# Sensor_Decoderv0_5.net
KiCad netlist of a schematic drawn in EAGLE
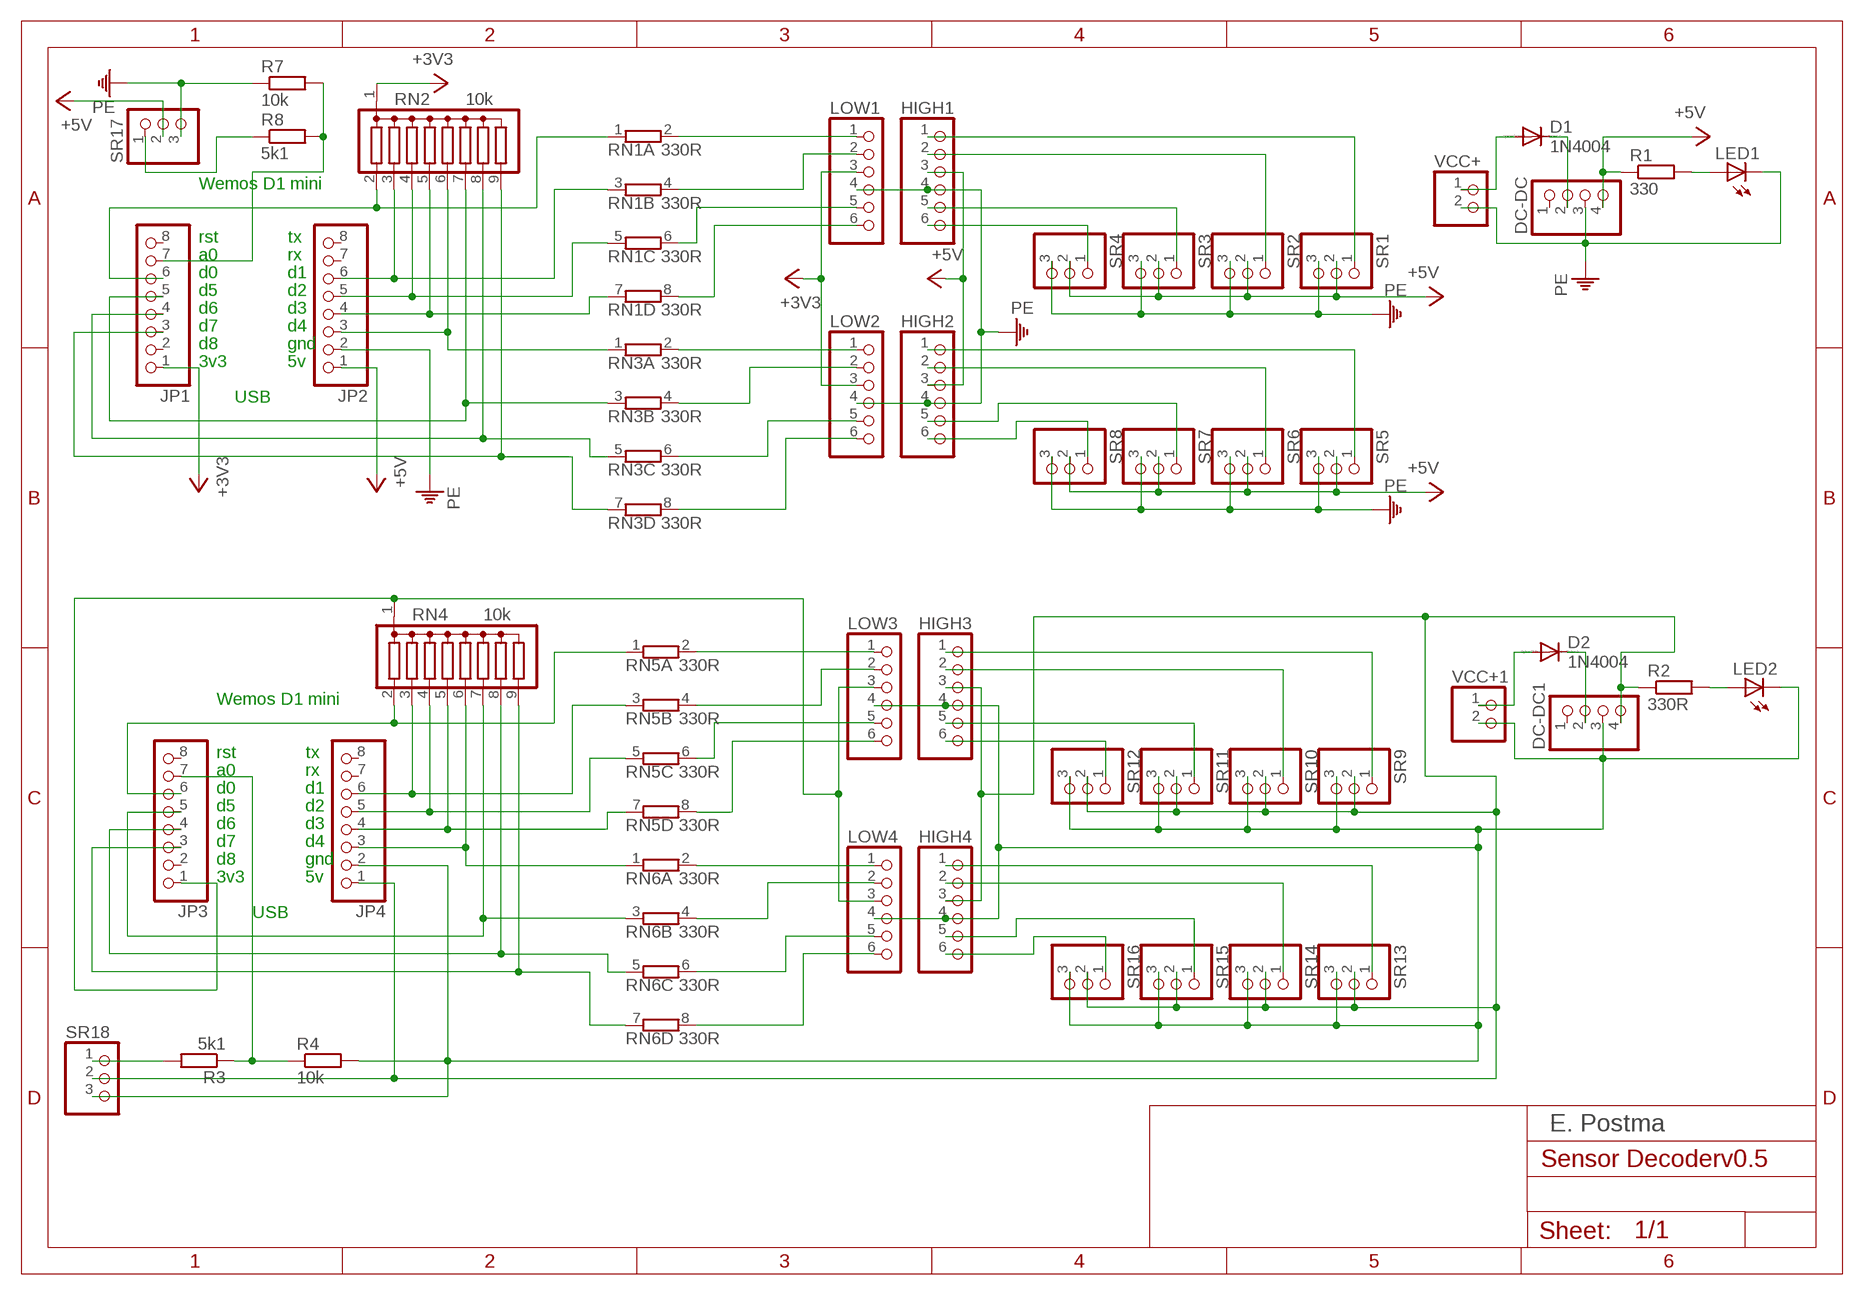
[diagram p0: schematic, sheet 1]

(export (version "E")
  (design (tool "Eeschema 10.0.6"))
  (components
    (comp (ref "D1")
      (value "1N4004")
      (footprint "eagle-import:DO41-10")
      (libsource (lib "eagle-import") (part "1N4004"))
    )
    (comp (ref "D2")
      (value "1N4004")
      (footprint "eagle-import:DO41-10")
      (libsource (lib "eagle-import") (part "1N4004"))
    )
    (comp (ref "DC-DC")
      (value "PINHD-1X4")
      (footprint "eagle-import:1X04")
      (libsource (lib "eagle-import") (part "PINHD-1X4"))
    )
    (comp (ref "DC-DC1")
      (value "PINHD-1X4")
      (footprint "eagle-import:1X04")
      (libsource (lib "eagle-import") (part "PINHD-1X4"))
    )
    (comp (ref "HIGH1")
      (value "PINHD-1X6")
      (footprint "eagle-import:1X06")
      (libsource (lib "eagle-import") (part "PINHD-1X6"))
    )
    (comp (ref "HIGH2")
      (value "PINHD-1X6")
      (footprint "eagle-import:1X06")
      (libsource (lib "eagle-import") (part "PINHD-1X6"))
    )
    (comp (ref "HIGH3")
      (value "PINHD-1X6")
      (footprint "eagle-import:1X06")
      (libsource (lib "eagle-import") (part "PINHD-1X6"))
    )
    (comp (ref "HIGH4")
      (value "PINHD-1X6")
      (footprint "eagle-import:1X06")
      (libsource (lib "eagle-import") (part "PINHD-1X6"))
    )
    (comp (ref "JP1")
      (value "PINHD-1X8")
      (footprint "eagle-import:1X08")
      (libsource (lib "eagle-import") (part "PINHD-1X8"))
    )
    (comp (ref "JP2")
      (value "PINHD-1X8")
      (footprint "eagle-import:1X08")
      (libsource (lib "eagle-import") (part "PINHD-1X8"))
    )
    (comp (ref "JP3")
      (value "PINHD-1X8")
      (footprint "eagle-import:1X08")
      (libsource (lib "eagle-import") (part "PINHD-1X8"))
    )
    (comp (ref "JP4")
      (value "PINHD-1X8")
      (footprint "eagle-import:1X08")
      (libsource (lib "eagle-import") (part "PINHD-1X8"))
    )
    (comp (ref "LED1")
      (value "LED3MM")
      (footprint "eagle-import:LED3MM")
      (libsource (lib "eagle-import") (part "LED3MM"))
    )
    (comp (ref "LED2")
      (value "LED3MM")
      (footprint "eagle-import:LED3MM")
      (libsource (lib "eagle-import") (part "LED3MM"))
    )
    (comp (ref "LOW1")
      (value "PINHD-1X6")
      (footprint "eagle-import:1X06")
      (libsource (lib "eagle-import") (part "PINHD-1X6"))
    )
    (comp (ref "LOW2")
      (value "PINHD-1X6")
      (footprint "eagle-import:1X06")
      (libsource (lib "eagle-import") (part "PINHD-1X6"))
    )
    (comp (ref "LOW3")
      (value "PINHD-1X6")
      (footprint "eagle-import:1X06")
      (libsource (lib "eagle-import") (part "PINHD-1X6"))
    )
    (comp (ref "LOW4")
      (value "PINHD-1X6")
      (footprint "eagle-import:1X06")
      (libsource (lib "eagle-import") (part "PINHD-1X6"))
    )
    (comp (ref "R1")
      (value "330")
      (footprint "eagle-import:0207_7")
      (libsource (lib "eagle-import") (part "R-EU_0207/7"))
    )
    (comp (ref "R2")
      (value "330R")
      (footprint "eagle-import:0207_7")
      (libsource (lib "eagle-import") (part "R-EU_0207/7"))
    )
    (comp (ref "R3")
      (value "5k1")
      (footprint "eagle-import:0207_7")
      (libsource (lib "eagle-import") (part "R-EU_0207/7"))
    )
    (comp (ref "R4")
      (value "10k")
      (footprint "eagle-import:0207_7")
      (libsource (lib "eagle-import") (part "R-EU_0207/7"))
    )
    (comp (ref "R7")
      (value "10k")
      (footprint "eagle-import:0207_7")
      (libsource (lib "eagle-import") (part "R-EU_0207/7"))
    )
    (comp (ref "R8")
      (value "5k1")
      (footprint "eagle-import:0207_7")
      (libsource (lib "eagle-import") (part "R-EU_0207/7"))
    )
    (comp (ref "RN1")
      (value "330R")
      (footprint "eagle-import:SIL8")
      (libsource (lib "eagle-import") (part "E4R"))
    )
    (comp (ref "RN2")
      (value "10k")
      (footprint "eagle-import:SIL9")
      (libsource (lib "eagle-import") (part "G08R"))
    )
    (comp (ref "RN3")
      (value "330R")
      (footprint "eagle-import:SIL8")
      (libsource (lib "eagle-import") (part "E4R"))
    )
    (comp (ref "RN4")
      (value "10k")
      (footprint "eagle-import:SIL9")
      (libsource (lib "eagle-import") (part "G08R"))
    )
    (comp (ref "RN5")
      (value "330R")
      (footprint "eagle-import:SIL8")
      (libsource (lib "eagle-import") (part "E4R"))
    )
    (comp (ref "RN6")
      (value "330R")
      (footprint "eagle-import:SIL8")
      (libsource (lib "eagle-import") (part "E4R"))
    )
    (comp (ref "SR1")
      (value "PINHD-1X3")
      (footprint "eagle-import:1X03")
      (libsource (lib "eagle-import") (part "PINHD-1X3"))
    )
    (comp (ref "SR2")
      (value "PINHD-1X3")
      (footprint "eagle-import:1X03")
      (libsource (lib "eagle-import") (part "PINHD-1X3"))
    )
    (comp (ref "SR3")
      (value "PINHD-1X3")
      (footprint "eagle-import:1X03")
      (libsource (lib "eagle-import") (part "PINHD-1X3"))
    )
    (comp (ref "SR4")
      (value "PINHD-1X3")
      (footprint "eagle-import:1X03")
      (libsource (lib "eagle-import") (part "PINHD-1X3"))
    )
    (comp (ref "SR5")
      (value "PINHD-1X3")
      (footprint "eagle-import:1X03")
      (libsource (lib "eagle-import") (part "PINHD-1X3"))
    )
    (comp (ref "SR6")
      (value "PINHD-1X3")
      (footprint "eagle-import:1X03")
      (libsource (lib "eagle-import") (part "PINHD-1X3"))
    )
    (comp (ref "SR7")
      (value "PINHD-1X3")
      (footprint "eagle-import:1X03")
      (libsource (lib "eagle-import") (part "PINHD-1X3"))
    )
    (comp (ref "SR8")
      (value "PINHD-1X3")
      (footprint "eagle-import:1X03")
      (libsource (lib "eagle-import") (part "PINHD-1X3"))
    )
    (comp (ref "SR9")
      (value "PINHD-1X3")
      (footprint "eagle-import:1X03")
      (libsource (lib "eagle-import") (part "PINHD-1X3"))
    )
    (comp (ref "SR10")
      (value "PINHD-1X3")
      (footprint "eagle-import:1X03")
      (libsource (lib "eagle-import") (part "PINHD-1X3"))
    )
    (comp (ref "SR11")
      (value "PINHD-1X3")
      (footprint "eagle-import:1X03")
      (libsource (lib "eagle-import") (part "PINHD-1X3"))
    )
    (comp (ref "SR12")
      (value "PINHD-1X3")
      (footprint "eagle-import:1X03")
      (libsource (lib "eagle-import") (part "PINHD-1X3"))
    )
    (comp (ref "SR13")
      (value "PINHD-1X3")
      (footprint "eagle-import:1X03")
      (libsource (lib "eagle-import") (part "PINHD-1X3"))
    )
    (comp (ref "SR14")
      (value "PINHD-1X3")
      (footprint "eagle-import:1X03")
      (libsource (lib "eagle-import") (part "PINHD-1X3"))
    )
    (comp (ref "SR15")
      (value "PINHD-1X3")
      (footprint "eagle-import:1X03")
      (libsource (lib "eagle-import") (part "PINHD-1X3"))
    )
    (comp (ref "SR16")
      (value "PINHD-1X3")
      (footprint "eagle-import:1X03")
      (libsource (lib "eagle-import") (part "PINHD-1X3"))
    )
    (comp (ref "SR17")
      (value "PINHD-1X3")
      (footprint "eagle-import:1X03")
      (libsource (lib "eagle-import") (part "PINHD-1X3"))
    )
    (comp (ref "SR18")
      (value "PINHD-1X3")
      (footprint "eagle-import:1X03")
      (libsource (lib "eagle-import") (part "PINHD-1X3"))
    )
    (comp (ref "VCC+")
      (value "PINHD-1X2")
      (footprint "eagle-import:1X02")
      (libsource (lib "eagle-import") (part "PINHD-1X2"))
    )
    (comp (ref "VCC+1")
      (value "PINHD-1X2")
      (footprint "eagle-import:1X02")
      (libsource (lib "eagle-import") (part "PINHD-1X2"))
    )
  )
  (nets
    (net (code "1") (name "+3V3") (class "Default")
      (node (ref "JP1") (pin "1") (pinfunction "1_1") (pintype "passive"))
      (node (ref "LOW1") (pin "3") (pinfunction "3_3") (pintype "passive"))
      (node (ref "LOW2") (pin "3") (pinfunction "3_3") (pintype "passive"))
      (node (ref "RN2") (pin "1") (pinfunction "1_1") (pintype "passive"))
    )
    (net (code "2") (name "+5V") (class "Default")
      (node (ref "DC-DC") (pin "4") (pinfunction "4_4") (pintype "passive"))
      (node (ref "HIGH1") (pin "3") (pinfunction "3_3") (pintype "passive"))
      (node (ref "HIGH2") (pin "3") (pinfunction "3_3") (pintype "passive"))
      (node (ref "JP2") (pin "1") (pinfunction "1_1") (pintype "passive"))
      (node (ref "R1") (pin "1") (pinfunction "1_1") (pintype "passive"))
      (node (ref "SR1") (pin "2") (pinfunction "2_2") (pintype "passive"))
      (node (ref "SR17") (pin "2") (pinfunction "2_2") (pintype "passive"))
      (node (ref "SR2") (pin "2") (pinfunction "2_2") (pintype "passive"))
      (node (ref "SR3") (pin "2") (pinfunction "2_2") (pintype "passive"))
      (node (ref "SR4") (pin "2") (pinfunction "2_2") (pintype "passive"))
      (node (ref "SR5") (pin "2") (pinfunction "2_2") (pintype "passive"))
      (node (ref "SR6") (pin "2") (pinfunction "2_2") (pintype "passive"))
      (node (ref "SR7") (pin "2") (pinfunction "2_2") (pintype "passive"))
      (node (ref "SR8") (pin "2") (pinfunction "2_2") (pintype "passive"))
    )
    (net (code "3") (name "Net-(D1-PadA)") (class "Default")
      (node (ref "D1") (pin "A") (pinfunction "A_A") (pintype "passive"))
      (node (ref "VCC+") (pin "1") (pinfunction "1_1") (pintype "passive"))
    )
    (net (code "4") (name "Net-(D1-PadC)") (class "Default")
      (node (ref "D1") (pin "C") (pinfunction "C_C") (pintype "passive"))
      (node (ref "DC-DC") (pin "2") (pinfunction "2_2") (pintype "passive"))
    )
    (net (code "5") (name "Net-(D2-PadA)") (class "Default")
      (node (ref "D2") (pin "A") (pinfunction "A_A") (pintype "passive"))
      (node (ref "VCC+1") (pin "1") (pinfunction "1_1") (pintype "passive"))
    )
    (net (code "6") (name "Net-(D2-PadC)") (class "Default")
      (node (ref "D2") (pin "C") (pinfunction "C_C") (pintype "passive"))
      (node (ref "DC-DC1") (pin "2") (pinfunction "2_2") (pintype "passive"))
    )
    (net (code "7") (name "Net-(DC-DC1-Pad4)") (class "Default")
      (node (ref "DC-DC1") (pin "4") (pinfunction "4_4") (pintype "passive"))
      (node (ref "HIGH3") (pin "3") (pinfunction "3_3") (pintype "passive"))
      (node (ref "HIGH4") (pin "3") (pinfunction "3_3") (pintype "passive"))
      (node (ref "JP4") (pin "1") (pinfunction "1_1") (pintype "passive"))
      (node (ref "R2") (pin "1") (pinfunction "1_1") (pintype "passive"))
      (node (ref "SR10") (pin "2") (pinfunction "2_2") (pintype "passive"))
      (node (ref "SR11") (pin "2") (pinfunction "2_2") (pintype "passive"))
      (node (ref "SR12") (pin "2") (pinfunction "2_2") (pintype "passive"))
      (node (ref "SR13") (pin "2") (pinfunction "2_2") (pintype "passive"))
      (node (ref "SR14") (pin "2") (pinfunction "2_2") (pintype "passive"))
      (node (ref "SR15") (pin "2") (pinfunction "2_2") (pintype "passive"))
      (node (ref "SR16") (pin "2") (pinfunction "2_2") (pintype "passive"))
      (node (ref "SR18") (pin "2") (pinfunction "2_2") (pintype "passive"))
      (node (ref "SR9") (pin "2") (pinfunction "2_2") (pintype "passive"))
    )
    (net (code "8") (name "Net-(HIGH1-Pad1)") (class "Default")
      (node (ref "HIGH1") (pin "1") (pinfunction "1_1") (pintype "passive"))
      (node (ref "SR1") (pin "1") (pinfunction "1_1") (pintype "passive"))
    )
    (net (code "9") (name "Net-(HIGH1-Pad2)") (class "Default")
      (node (ref "HIGH1") (pin "2") (pinfunction "2_2") (pintype "passive"))
      (node (ref "SR2") (pin "1") (pinfunction "1_1") (pintype "passive"))
    )
    (net (code "10") (name "Net-(HIGH1-Pad5)") (class "Default")
      (node (ref "HIGH1") (pin "5") (pinfunction "5_5") (pintype "passive"))
      (node (ref "SR3") (pin "1") (pinfunction "1_1") (pintype "passive"))
    )
    (net (code "11") (name "Net-(HIGH1-Pad6)") (class "Default")
      (node (ref "HIGH1") (pin "6") (pinfunction "6_6") (pintype "passive"))
      (node (ref "SR4") (pin "1") (pinfunction "1_1") (pintype "passive"))
    )
    (net (code "12") (name "Net-(HIGH2-Pad1)") (class "Default")
      (node (ref "HIGH2") (pin "1") (pinfunction "1_1") (pintype "passive"))
      (node (ref "SR5") (pin "1") (pinfunction "1_1") (pintype "passive"))
    )
    (net (code "13") (name "Net-(HIGH2-Pad2)") (class "Default")
      (node (ref "HIGH2") (pin "2") (pinfunction "2_2") (pintype "passive"))
      (node (ref "SR6") (pin "1") (pinfunction "1_1") (pintype "passive"))
    )
    (net (code "14") (name "Net-(HIGH2-Pad5)") (class "Default")
      (node (ref "HIGH2") (pin "5") (pinfunction "5_5") (pintype "passive"))
      (node (ref "SR7") (pin "1") (pinfunction "1_1") (pintype "passive"))
    )
    (net (code "15") (name "Net-(HIGH2-Pad6)") (class "Default")
      (node (ref "HIGH2") (pin "6") (pinfunction "6_6") (pintype "passive"))
      (node (ref "SR8") (pin "1") (pinfunction "1_1") (pintype "passive"))
    )
    (net (code "16") (name "Net-(HIGH3-Pad1)") (class "Default")
      (node (ref "HIGH3") (pin "1") (pinfunction "1_1") (pintype "passive"))
      (node (ref "SR9") (pin "1") (pinfunction "1_1") (pintype "passive"))
    )
    (net (code "17") (name "Net-(HIGH3-Pad2)") (class "Default")
      (node (ref "HIGH3") (pin "2") (pinfunction "2_2") (pintype "passive"))
      (node (ref "SR10") (pin "1") (pinfunction "1_1") (pintype "passive"))
    )
    (net (code "18") (name "Net-(HIGH3-Pad5)") (class "Default")
      (node (ref "HIGH3") (pin "5") (pinfunction "5_5") (pintype "passive"))
      (node (ref "SR11") (pin "1") (pinfunction "1_1") (pintype "passive"))
    )
    (net (code "19") (name "Net-(HIGH3-Pad6)") (class "Default")
      (node (ref "HIGH3") (pin "6") (pinfunction "6_6") (pintype "passive"))
      (node (ref "SR12") (pin "1") (pinfunction "1_1") (pintype "passive"))
    )
    (net (code "20") (name "Net-(HIGH4-Pad1)") (class "Default")
      (node (ref "HIGH4") (pin "1") (pinfunction "1_1") (pintype "passive"))
      (node (ref "SR13") (pin "1") (pinfunction "1_1") (pintype "passive"))
    )
    (net (code "21") (name "Net-(HIGH4-Pad2)") (class "Default")
      (node (ref "HIGH4") (pin "2") (pinfunction "2_2") (pintype "passive"))
      (node (ref "SR14") (pin "1") (pinfunction "1_1") (pintype "passive"))
    )
    (net (code "22") (name "Net-(HIGH4-Pad5)") (class "Default")
      (node (ref "HIGH4") (pin "5") (pinfunction "5_5") (pintype "passive"))
      (node (ref "SR15") (pin "1") (pinfunction "1_1") (pintype "passive"))
    )
    (net (code "23") (name "Net-(HIGH4-Pad6)") (class "Default")
      (node (ref "HIGH4") (pin "6") (pinfunction "6_6") (pintype "passive"))
      (node (ref "SR16") (pin "1") (pinfunction "1_1") (pintype "passive"))
    )
    (net (code "24") (name "Net-(JP1-Pad6)") (class "Default")
      (node (ref "JP1") (pin "6") (pinfunction "6_6") (pintype "passive"))
      (node (ref "RN1") (pin "1") (pinfunction "1_1") (pintype "passive"))
      (node (ref "RN2") (pin "2") (pinfunction "2_2") (pintype "passive"))
    )
    (net (code "25") (name "Net-(JP1-Pad7)") (class "Default")
      (node (ref "JP1") (pin "7") (pinfunction "7_7") (pintype "passive"))
      (node (ref "R7") (pin "2") (pinfunction "2_2") (pintype "passive"))
      (node (ref "R8") (pin "2") (pinfunction "2_2") (pintype "passive"))
    )
    (net (code "26") (name "Net-(JP2-Pad3)") (class "Default")
      (node (ref "JP2") (pin "3") (pinfunction "3_3") (pintype "passive"))
      (node (ref "RN2") (pin "6") (pinfunction "6_6") (pintype "passive"))
      (node (ref "RN3") (pin "1") (pinfunction "1_1") (pintype "passive"))
    )
    (net (code "27") (name "Net-(JP3-Pad1)") (class "Default")
      (node (ref "JP3") (pin "1") (pinfunction "1_1") (pintype "passive"))
      (node (ref "LOW3") (pin "3") (pinfunction "3_3") (pintype "passive"))
      (node (ref "LOW4") (pin "3") (pinfunction "3_3") (pintype "passive"))
      (node (ref "RN4") (pin "1") (pinfunction "1_1") (pintype "passive"))
    )
    (net (code "28") (name "Net-(JP3-Pad6)") (class "Default")
      (node (ref "JP3") (pin "6") (pinfunction "6_6") (pintype "passive"))
      (node (ref "RN4") (pin "2") (pinfunction "2_2") (pintype "passive"))
      (node (ref "RN5") (pin "1") (pinfunction "1_1") (pintype "passive"))
    )
    (net (code "29") (name "Net-(JP3-Pad7)") (class "Default")
      (node (ref "JP3") (pin "7") (pinfunction "7_7") (pintype "passive"))
      (node (ref "R3") (pin "1") (pinfunction "1_1") (pintype "passive"))
      (node (ref "R4") (pin "1") (pinfunction "1_1") (pintype "passive"))
    )
    (net (code "30") (name "Net-(JP4-Pad3)") (class "Default")
      (node (ref "JP4") (pin "3") (pinfunction "3_3") (pintype "passive"))
      (node (ref "RN4") (pin "6") (pinfunction "6_6") (pintype "passive"))
      (node (ref "RN6") (pin "1") (pinfunction "1_1") (pintype "passive"))
    )
    (net (code "31") (name "Net-(LED1-PadA)") (class "Default")
      (node (ref "LED1") (pin "A") (pinfunction "A_A") (pintype "passive"))
      (node (ref "R1") (pin "2") (pinfunction "2_2") (pintype "passive"))
    )
    (net (code "32") (name "Net-(LED2-C)") (class "Default")
      (node (ref "DC-DC1") (pin "3") (pinfunction "3_3") (pintype "passive"))
      (node (ref "HIGH3") (pin "4") (pinfunction "4_4") (pintype "passive"))
      (node (ref "HIGH4") (pin "4") (pinfunction "4_4") (pintype "passive"))
      (node (ref "JP4") (pin "2") (pinfunction "2_2") (pintype "passive"))
      (node (ref "LED2") (pin "K") (pinfunction "C_K") (pintype "passive"))
      (node (ref "LOW3") (pin "4") (pinfunction "4_4") (pintype "passive"))
      (node (ref "LOW4") (pin "4") (pinfunction "4_4") (pintype "passive"))
      (node (ref "R4") (pin "2") (pinfunction "2_2") (pintype "passive"))
      (node (ref "SR10") (pin "3") (pinfunction "3_3") (pintype "passive"))
      (node (ref "SR11") (pin "3") (pinfunction "3_3") (pintype "passive"))
      (node (ref "SR12") (pin "3") (pinfunction "3_3") (pintype "passive"))
      (node (ref "SR13") (pin "3") (pinfunction "3_3") (pintype "passive"))
      (node (ref "SR14") (pin "3") (pinfunction "3_3") (pintype "passive"))
      (node (ref "SR15") (pin "3") (pinfunction "3_3") (pintype "passive"))
      (node (ref "SR16") (pin "3") (pinfunction "3_3") (pintype "passive"))
      (node (ref "SR18") (pin "3") (pinfunction "3_3") (pintype "passive"))
      (node (ref "SR9") (pin "3") (pinfunction "3_3") (pintype "passive"))
      (node (ref "VCC+1") (pin "2") (pinfunction "2_2") (pintype "passive"))
    )
    (net (code "33") (name "Net-(LED2-PadA)") (class "Default")
      (node (ref "LED2") (pin "A") (pinfunction "A_A") (pintype "passive"))
      (node (ref "R2") (pin "2") (pinfunction "2_2") (pintype "passive"))
    )
    (net (code "34") (name "Net-(LOW1-Pad1)") (class "Default")
      (node (ref "LOW1") (pin "1") (pinfunction "1_1") (pintype "passive"))
      (node (ref "RN1") (pin "2") (pinfunction "2_2") (pintype "passive"))
    )
    (net (code "35") (name "Net-(LOW2-Pad1)") (class "Default")
      (node (ref "LOW2") (pin "1") (pinfunction "1_1") (pintype "passive"))
      (node (ref "RN3") (pin "2") (pinfunction "2_2") (pintype "passive"))
    )
    (net (code "36") (name "Net-(LOW3-Pad1)") (class "Default")
      (node (ref "LOW3") (pin "1") (pinfunction "1_1") (pintype "passive"))
      (node (ref "RN5") (pin "2") (pinfunction "2_2") (pintype "passive"))
    )
    (net (code "37") (name "Net-(LOW4-Pad1)") (class "Default")
      (node (ref "LOW4") (pin "1") (pinfunction "1_1") (pintype "passive"))
      (node (ref "RN6") (pin "2") (pinfunction "2_2") (pintype "passive"))
    )
    (net (code "38") (name "Net-(R3-Pad2)") (class "Default")
      (node (ref "R3") (pin "2") (pinfunction "2_2") (pintype "passive"))
      (node (ref "SR18") (pin "1") (pinfunction "1_1") (pintype "passive"))
    )
    (net (code "39") (name "Net-(R8-Pad1)") (class "Default")
      (node (ref "R8") (pin "1") (pinfunction "1_1") (pintype "passive"))
      (node (ref "SR17") (pin "1") (pinfunction "1_1") (pintype "passive"))
    )
    (net (code "40") (name "Net-(RN1B-1)") (class "Default")
      (node (ref "JP2") (pin "6") (pinfunction "6_6") (pintype "passive"))
      (node (ref "RN1") (pin "3") (pinfunction "1_3") (pintype "passive"))
      (node (ref "RN2") (pin "3") (pinfunction "3_3") (pintype "passive"))
    )
    (net (code "41") (name "Net-(RN1B-2)") (class "Default")
      (node (ref "LOW1") (pin "2") (pinfunction "2_2") (pintype "passive"))
      (node (ref "RN1") (pin "4") (pinfunction "2_4") (pintype "passive"))
    )
    (net (code "42") (name "Net-(RN1C-1)") (class "Default")
      (node (ref "JP2") (pin "5") (pinfunction "5_5") (pintype "passive"))
      (node (ref "RN1") (pin "5") (pinfunction "1_5") (pintype "passive"))
      (node (ref "RN2") (pin "4") (pinfunction "4_4") (pintype "passive"))
    )
    (net (code "43") (name "Net-(RN1C-2)") (class "Default")
      (node (ref "LOW1") (pin "5") (pinfunction "5_5") (pintype "passive"))
      (node (ref "RN1") (pin "6") (pinfunction "2_6") (pintype "passive"))
    )
    (net (code "44") (name "Net-(RN1D-1)") (class "Default")
      (node (ref "JP2") (pin "4") (pinfunction "4_4") (pintype "passive"))
      (node (ref "RN1") (pin "7") (pinfunction "1_7") (pintype "passive"))
      (node (ref "RN2") (pin "5") (pinfunction "5_5") (pintype "passive"))
    )
    (net (code "45") (name "Net-(RN1D-2)") (class "Default")
      (node (ref "LOW1") (pin "6") (pinfunction "6_6") (pintype "passive"))
      (node (ref "RN1") (pin "8") (pinfunction "2_8") (pintype "passive"))
    )
    (net (code "46") (name "Net-(RN3B-1)") (class "Default")
      (node (ref "JP1") (pin "5") (pinfunction "5_5") (pintype "passive"))
      (node (ref "RN2") (pin "7") (pinfunction "7_7") (pintype "passive"))
      (node (ref "RN3") (pin "3") (pinfunction "1_3") (pintype "passive"))
    )
    (net (code "47") (name "Net-(RN3B-2)") (class "Default")
      (node (ref "LOW2") (pin "2") (pinfunction "2_2") (pintype "passive"))
      (node (ref "RN3") (pin "4") (pinfunction "2_4") (pintype "passive"))
    )
    (net (code "48") (name "Net-(RN3C-1)") (class "Default")
      (node (ref "JP1") (pin "4") (pinfunction "4_4") (pintype "passive"))
      (node (ref "RN2") (pin "8") (pinfunction "8_8") (pintype "passive"))
      (node (ref "RN3") (pin "5") (pinfunction "1_5") (pintype "passive"))
    )
    (net (code "49") (name "Net-(RN3C-2)") (class "Default")
      (node (ref "LOW2") (pin "5") (pinfunction "5_5") (pintype "passive"))
      (node (ref "RN3") (pin "6") (pinfunction "2_6") (pintype "passive"))
    )
    (net (code "50") (name "Net-(RN3D-1)") (class "Default")
      (node (ref "JP1") (pin "3") (pinfunction "3_3") (pintype "passive"))
      (node (ref "RN2") (pin "9") (pinfunction "9_9") (pintype "passive"))
      (node (ref "RN3") (pin "7") (pinfunction "1_7") (pintype "passive"))
    )
    (net (code "51") (name "Net-(RN3D-2)") (class "Default")
      (node (ref "LOW2") (pin "6") (pinfunction "6_6") (pintype "passive"))
      (node (ref "RN3") (pin "8") (pinfunction "2_8") (pintype "passive"))
    )
    (net (code "52") (name "Net-(RN5B-1)") (class "Default")
      (node (ref "JP4") (pin "6") (pinfunction "6_6") (pintype "passive"))
      (node (ref "RN4") (pin "3") (pinfunction "3_3") (pintype "passive"))
      (node (ref "RN5") (pin "3") (pinfunction "1_3") (pintype "passive"))
    )
    (net (code "53") (name "Net-(RN5B-2)") (class "Default")
      (node (ref "LOW3") (pin "2") (pinfunction "2_2") (pintype "passive"))
      (node (ref "RN5") (pin "4") (pinfunction "2_4") (pintype "passive"))
    )
    (net (code "54") (name "Net-(RN5C-1)") (class "Default")
      (node (ref "JP4") (pin "5") (pinfunction "5_5") (pintype "passive"))
      (node (ref "RN4") (pin "4") (pinfunction "4_4") (pintype "passive"))
      (node (ref "RN5") (pin "5") (pinfunction "1_5") (pintype "passive"))
    )
    (net (code "55") (name "Net-(RN5C-2)") (class "Default")
      (node (ref "LOW3") (pin "5") (pinfunction "5_5") (pintype "passive"))
      (node (ref "RN5") (pin "6") (pinfunction "2_6") (pintype "passive"))
    )
    (net (code "56") (name "Net-(RN5D-1)") (class "Default")
      (node (ref "JP4") (pin "4") (pinfunction "4_4") (pintype "passive"))
      (node (ref "RN4") (pin "5") (pinfunction "5_5") (pintype "passive"))
      (node (ref "RN5") (pin "7") (pinfunction "1_7") (pintype "passive"))
    )
    (net (code "57") (name "Net-(RN5D-2)") (class "Default")
      (node (ref "LOW3") (pin "6") (pinfunction "6_6") (pintype "passive"))
      (node (ref "RN5") (pin "8") (pinfunction "2_8") (pintype "passive"))
    )
    (net (code "58") (name "Net-(RN6B-1)") (class "Default")
      (node (ref "JP3") (pin "5") (pinfunction "5_5") (pintype "passive"))
      (node (ref "RN4") (pin "7") (pinfunction "7_7") (pintype "passive"))
      (node (ref "RN6") (pin "3") (pinfunction "1_3") (pintype "passive"))
    )
    (net (code "59") (name "Net-(RN6B-2)") (class "Default")
      (node (ref "LOW4") (pin "2") (pinfunction "2_2") (pintype "passive"))
      (node (ref "RN6") (pin "4") (pinfunction "2_4") (pintype "passive"))
    )
    (net (code "60") (name "Net-(RN6C-1)") (class "Default")
      (node (ref "JP3") (pin "4") (pinfunction "4_4") (pintype "passive"))
      (node (ref "RN4") (pin "8") (pinfunction "8_8") (pintype "passive"))
      (node (ref "RN6") (pin "5") (pinfunction "1_5") (pintype "passive"))
    )
    (net (code "61") (name "Net-(RN6C-2)") (class "Default")
      (node (ref "LOW4") (pin "5") (pinfunction "5_5") (pintype "passive"))
      (node (ref "RN6") (pin "6") (pinfunction "2_6") (pintype "passive"))
    )
    (net (code "62") (name "Net-(RN6D-1)") (class "Default")
      (node (ref "JP3") (pin "3") (pinfunction "3_3") (pintype "passive"))
      (node (ref "RN4") (pin "9") (pinfunction "9_9") (pintype "passive"))
      (node (ref "RN6") (pin "7") (pinfunction "1_7") (pintype "passive"))
    )
    (net (code "63") (name "Net-(RN6D-2)") (class "Default")
      (node (ref "LOW4") (pin "6") (pinfunction "6_6") (pintype "passive"))
      (node (ref "RN6") (pin "8") (pinfunction "2_8") (pintype "passive"))
    )
    (net (code "64") (name "PE") (class "Default")
      (node (ref "DC-DC") (pin "3") (pinfunction "3_3") (pintype "passive"))
      (node (ref "HIGH1") (pin "4") (pinfunction "4_4") (pintype "passive"))
      (node (ref "HIGH2") (pin "4") (pinfunction "4_4") (pintype "passive"))
      (node (ref "JP2") (pin "2") (pinfunction "2_2") (pintype "passive"))
      (node (ref "LED1") (pin "K") (pinfunction "C_K") (pintype "passive"))
      (node (ref "LOW1") (pin "4") (pinfunction "4_4") (pintype "passive"))
      (node (ref "LOW2") (pin "4") (pinfunction "4_4") (pintype "passive"))
      (node (ref "R7") (pin "1") (pinfunction "1_1") (pintype "passive"))
      (node (ref "SR1") (pin "3") (pinfunction "3_3") (pintype "passive"))
      (node (ref "SR17") (pin "3") (pinfunction "3_3") (pintype "passive"))
      (node (ref "SR2") (pin "3") (pinfunction "3_3") (pintype "passive"))
      (node (ref "SR3") (pin "3") (pinfunction "3_3") (pintype "passive"))
      (node (ref "SR4") (pin "3") (pinfunction "3_3") (pintype "passive"))
      (node (ref "SR5") (pin "3") (pinfunction "3_3") (pintype "passive"))
      (node (ref "SR6") (pin "3") (pinfunction "3_3") (pintype "passive"))
      (node (ref "SR7") (pin "3") (pinfunction "3_3") (pintype "passive"))
      (node (ref "SR8") (pin "3") (pinfunction "3_3") (pintype "passive"))
      (node (ref "VCC+") (pin "2") (pinfunction "2_2") (pintype "passive"))
    )
    (net (code "65") (name "unconnected-(DC-DC-Pad1)") (class "Default")
      (node (ref "DC-DC") (pin "1") (pinfunction "1_1") (pintype "passive"))
    )
    (net (code "66") (name "unconnected-(DC-DC1-Pad1)") (class "Default")
      (node (ref "DC-DC1") (pin "1") (pinfunction "1_1") (pintype "passive"))
    )
    (net (code "67") (name "unconnected-(JP1-Pad2)") (class "Default")
      (node (ref "JP1") (pin "2") (pinfunction "2_2") (pintype "passive"))
    )
    (net (code "68") (name "unconnected-(JP1-Pad8)") (class "Default")
      (node (ref "JP1") (pin "8") (pinfunction "8_8") (pintype "passive"))
    )
    (net (code "69") (name "unconnected-(JP2-Pad7)") (class "Default")
      (node (ref "JP2") (pin "7") (pinfunction "7_7") (pintype "passive"))
    )
    (net (code "70") (name "unconnected-(JP2-Pad8)") (class "Default")
      (node (ref "JP2") (pin "8") (pinfunction "8_8") (pintype "passive"))
    )
    (net (code "71") (name "unconnected-(JP3-Pad2)") (class "Default")
      (node (ref "JP3") (pin "2") (pinfunction "2_2") (pintype "passive"))
    )
    (net (code "72") (name "unconnected-(JP3-Pad8)") (class "Default")
      (node (ref "JP3") (pin "8") (pinfunction "8_8") (pintype "passive"))
    )
    (net (code "73") (name "unconnected-(JP4-Pad7)") (class "Default")
      (node (ref "JP4") (pin "7") (pinfunction "7_7") (pintype "passive"))
    )
    (net (code "74") (name "unconnected-(JP4-Pad8)") (class "Default")
      (node (ref "JP4") (pin "8") (pinfunction "8_8") (pintype "passive"))
    )
  )
)
